# MEchaduino_03.net
KiCad netlist of a schematic drawn in EAGLE
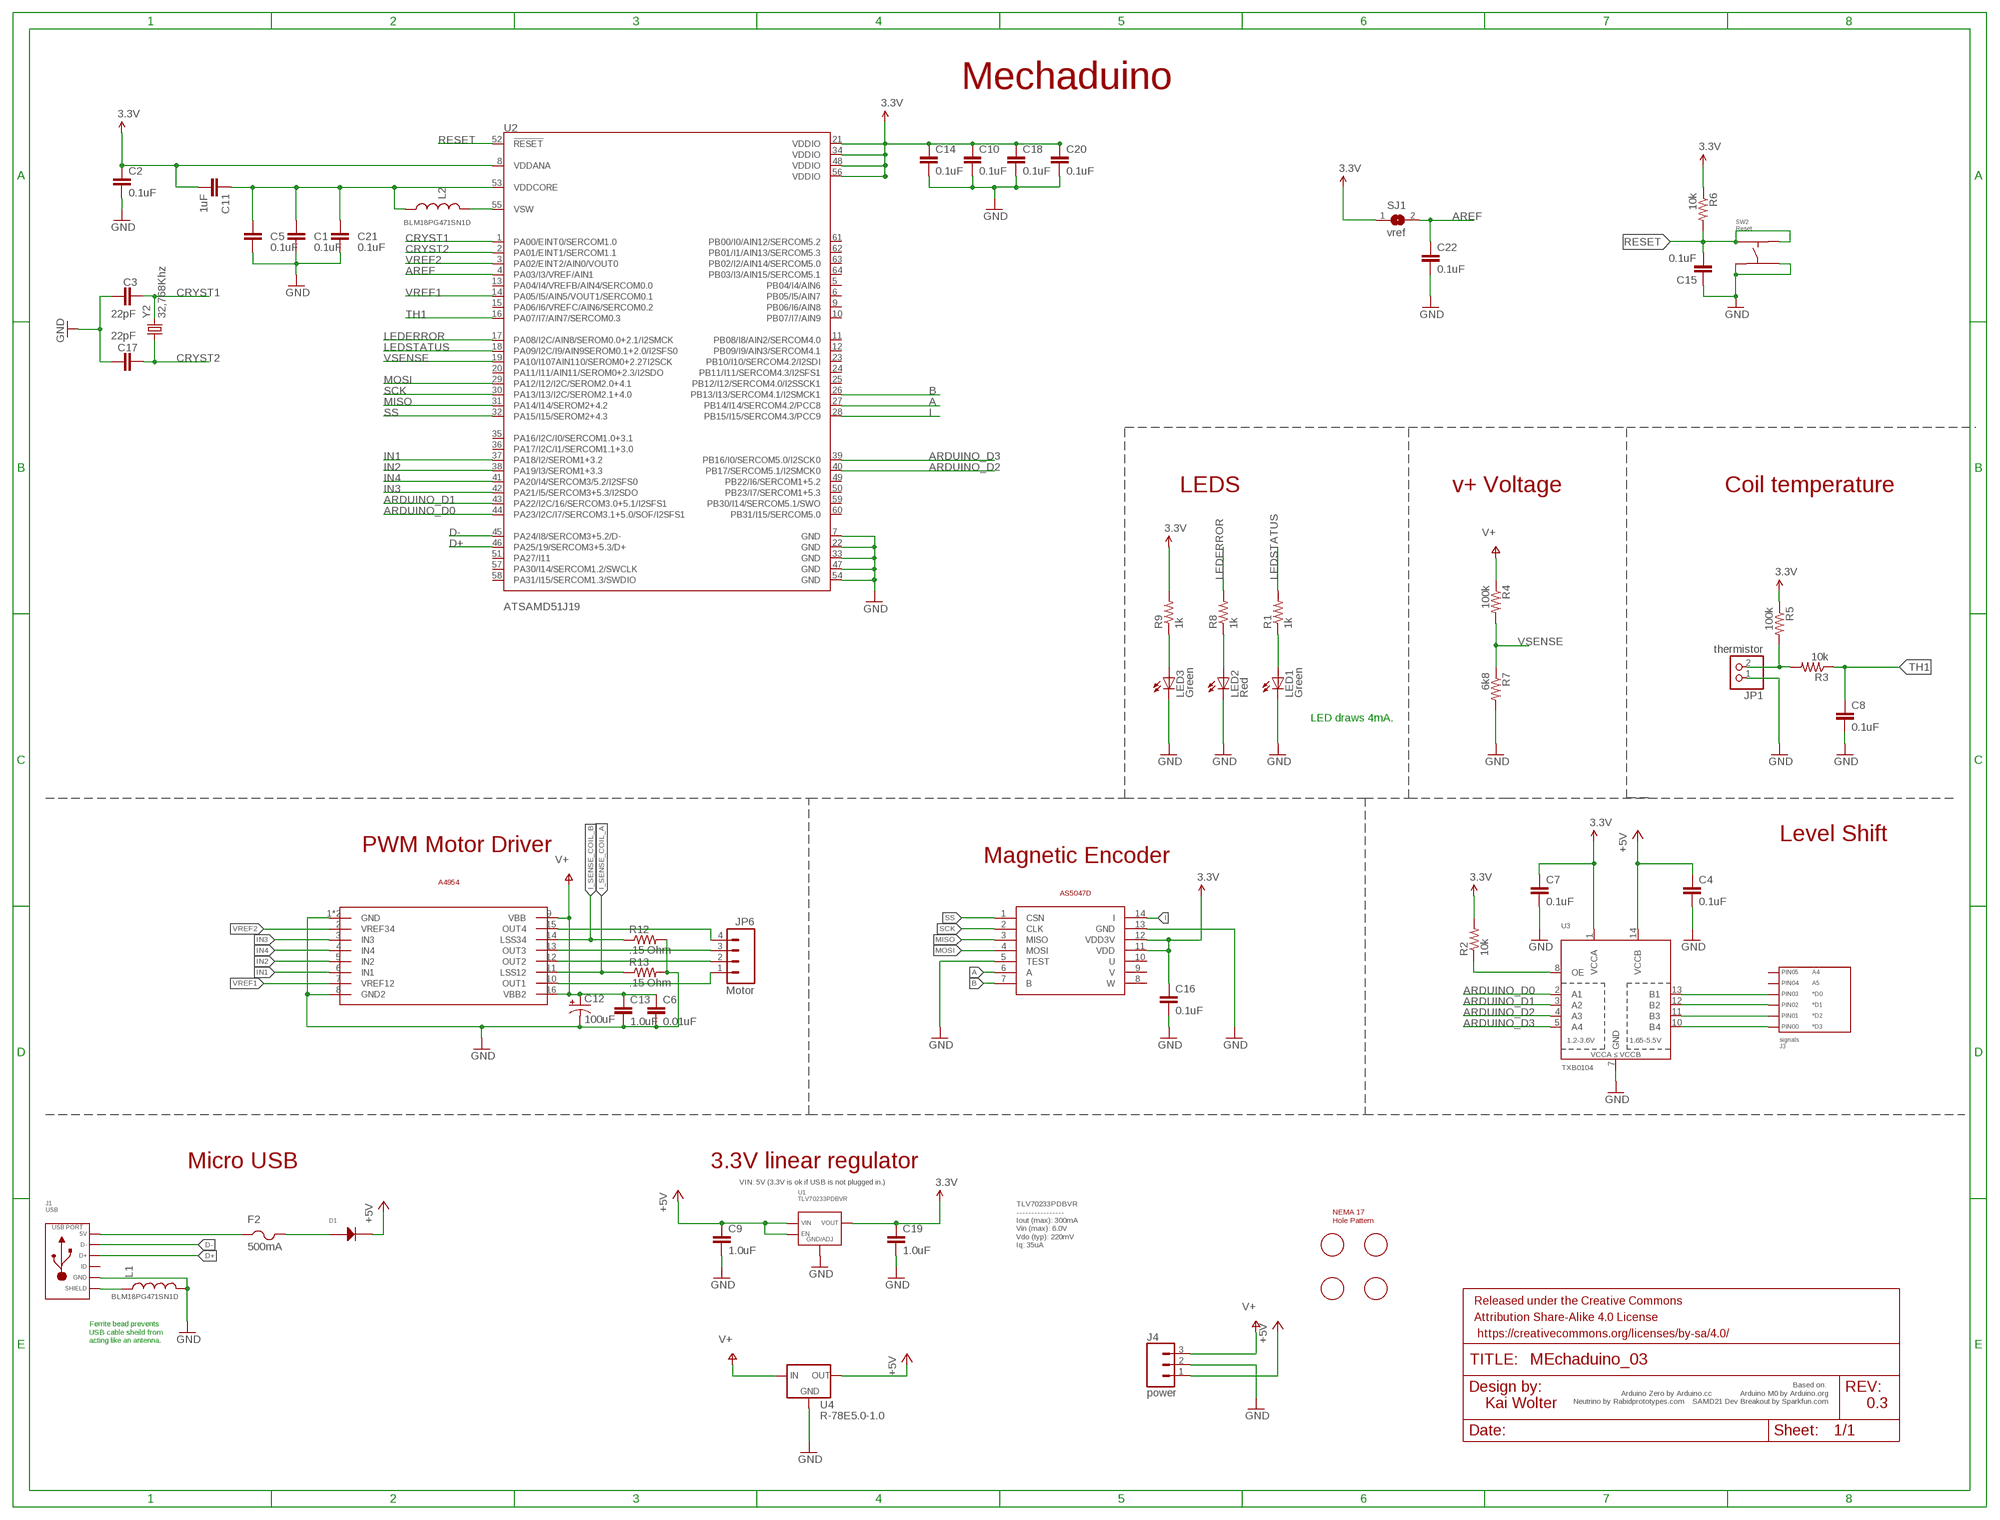
[diagram p0: schematic, sheet 1]

(export (version "E")
  (design (tool "Eeschema 10.0.6"))
  (components
    (comp (ref "C1")
      (value "0.1uF")
      (footprint "eagle-import:0402-CAP")
      (libsource (lib "eagle-import") (part "CAP0402"))
    )
    (comp (ref "C2")
      (value "0.1uF")
      (footprint "eagle-import:0402-CAP")
      (libsource (lib "eagle-import") (part "CAP0402"))
    )
    (comp (ref "C3")
      (value "22pF")
      (footprint "eagle-import:0603-CAP")
      (libsource (lib "eagle-import") (part "CAP0603"))
    )
    (comp (ref "C4")
      (value "0.1uF")
      (footprint "eagle-import:0402-CAP")
      (libsource (lib "eagle-import") (part "CAP0402"))
    )
    (comp (ref "C5")
      (value "0.1uF")
      (footprint "eagle-import:0402-CAP")
      (libsource (lib "eagle-import") (part "CAP0402"))
    )
    (comp (ref "C6")
      (value "0.01uF")
      (footprint "eagle-import:0603-CAP")
      (libsource (lib "eagle-import") (part "CAP0603"))
    )
    (comp (ref "C7")
      (value "0.1uF")
      (footprint "eagle-import:0402-CAP")
      (libsource (lib "eagle-import") (part "CAP0402"))
    )
    (comp (ref "C8")
      (value "0.1uF")
      (footprint "eagle-import:0402-CAP")
      (libsource (lib "eagle-import") (part "CAP0402"))
    )
    (comp (ref "C9")
      (value "1.0uF")
      (footprint "eagle-import:0402-CAP")
      (libsource (lib "eagle-import") (part "CAP0402"))
    )
    (comp (ref "C10")
      (value "0.1uF")
      (footprint "eagle-import:0402-CAP")
      (libsource (lib "eagle-import") (part "CAP0402"))
    )
    (comp (ref "C11")
      (value "1uF")
      (footprint "eagle-import:0402-CAP")
      (libsource (lib "eagle-import") (part "CAP0402"))
    )
    (comp (ref "C12")
      (value "100uF")
      (footprint "eagle-import:PANASONIC_D")
      (libsource (lib "eagle-import") (part "CAP_POLD"))
    )
    (comp (ref "C13")
      (value "1.0uF")
      (footprint "eagle-import:0603-CAP")
      (libsource (lib "eagle-import") (part "CAP0603"))
    )
    (comp (ref "C14")
      (value "0.1uF")
      (footprint "eagle-import:0402-CAP")
      (libsource (lib "eagle-import") (part "CAP0402"))
    )
    (comp (ref "C15")
      (value "0.1uF")
      (footprint "eagle-import:0402-CAP")
      (libsource (lib "eagle-import") (part "CAP0402"))
    )
    (comp (ref "C16")
      (value "0.1uF")
      (footprint "eagle-import:0402-CAP")
      (libsource (lib "eagle-import") (part "CAP0402"))
    )
    (comp (ref "C17")
      (value "22pF")
      (footprint "eagle-import:0603-CAP")
      (libsource (lib "eagle-import") (part "CAP0603"))
    )
    (comp (ref "C18")
      (value "0.1uF")
      (footprint "eagle-import:0402-CAP")
      (libsource (lib "eagle-import") (part "CAP0402"))
    )
    (comp (ref "C19")
      (value "1.0uF")
      (footprint "eagle-import:0402-CAP")
      (libsource (lib "eagle-import") (part "CAP0402"))
    )
    (comp (ref "C20")
      (value "0.1uF")
      (footprint "eagle-import:0402-CAP")
      (libsource (lib "eagle-import") (part "CAP0402"))
    )
    (comp (ref "C21")
      (value "0.1uF")
      (footprint "eagle-import:0402-CAP")
      (libsource (lib "eagle-import") (part "CAP0402"))
    )
    (comp (ref "C22")
      (value "0.1uF")
      (footprint "eagle-import:0402-CAP")
      (libsource (lib "eagle-import") (part "CAP0402"))
    )
    (comp (ref "D1")
      (value "DIODE_SOD-123")
      (footprint "eagle-import:SOD-123")
      (libsource (lib "eagle-import") (part "DIODE_SOD-123"))
    )
    (comp (ref "F2")
      (value "500mA")
      (footprint "eagle-import:R1206")
      (libsource (lib "eagle-import") (part "PTCFUSE-1206"))
    )
    (comp (ref "FRAME1")
      (value "FRAME-LEDGER")
      (footprint "eagle-import:CREATIVE_COMMONS")
      (libsource (lib "eagle-import") (part "FRAME-LEDGER"))
    )
    (comp (ref "J1")
      (value "USB")
      (footprint "eagle-import:MICROUSB-RIGHT")
      (libsource (lib "eagle-import") (part "USB_MICRO_RIGHT"))
    )
    (comp (ref "J3")
      (value "signals")
      (footprint "eagle-import:PTH_2.54MM_01X06")
      (fields
        (field (name "LABEL00") "*D3")
        (field (name "LABEL01") "*D2")
        (field (name "LABEL02") "*D1")
        (field (name "LABEL03") "*D0")
        (field (name "LABEL04") "A5")
        (field (name "LABEL05") "A4")
      )
      (libsource (lib "eagle-import") (part "HEADER_01X06_PTH_2.54MM"))
    )
    (comp (ref "J4")
      (value "power")
      (footprint "eagle-import:1X03")
      (libsource (lib "eagle-import") (part "CONN_03"))
    )
    (comp (ref "JP1")
      (value "thermistor")
      (footprint "eagle-import:1X02")
      (libsource (lib "eagle-import") (part "PINHD-1X2"))
    )
    (comp (ref "JP6")
      (value "Motor")
      (footprint "eagle-import:1X04")
      (libsource (lib "eagle-import") (part "M04PTH"))
    )
    (comp (ref "L1")
      (value "BLM18PG471SN1D")
      (footprint "eagle-import:0603-TDK")
      (libsource (lib "eagle-import") (part "INDUCTOR0603-TDK"))
    )
    (comp (ref "L2")
      (value "BLM18PG471SN1D")
      (footprint "eagle-import:0603-TDK")
      (libsource (lib "eagle-import") (part "INDUCTOR0603-TDK"))
    )
    (comp (ref "LED1")
      (value "Green")
      (footprint "eagle-import:CHIPLED_0805")
      (fields (field (name "PART_NUMBER") "KPT-2012YC"))
      (libsource (lib "eagle-import") (part "0044_KPT-2012YC"))
    )
    (comp (ref "LED2")
      (value "Red")
      (footprint "eagle-import:CHIPLED_0805")
      (fields (field (name "PART_NUMBER") "KPT-2012YC"))
      (libsource (lib "eagle-import") (part "0044_KPT-2012YC"))
    )
    (comp (ref "LED3")
      (value "Green")
      (footprint "eagle-import:CHIPLED_0805")
      (fields (field (name "PART_NUMBER") "KPT-2012YC"))
      (libsource (lib "eagle-import") (part "0044_KPT-2012YC"))
    )
    (comp (ref "R1")
      (value "1k")
      (footprint "eagle-import:R0402")
      (libsource (lib "eagle-import") (part "rcl_334_R-US_R0402"))
    )
    (comp (ref "R2")
      (value "10k")
      (footprint "eagle-import:R0402")
      (libsource (lib "eagle-import") (part "rcl_334_R-US_R0402"))
    )
    (comp (ref "R3")
      (value "10k")
      (footprint "eagle-import:R0402")
      (libsource (lib "eagle-import") (part "rcl_334_R-US_R0402"))
    )
    (comp (ref "R4")
      (value "100k")
      (footprint "eagle-import:R0402")
      (libsource (lib "eagle-import") (part "rcl_334_R-US_R0402"))
    )
    (comp (ref "R5")
      (value "100k")
      (footprint "eagle-import:R0402")
      (libsource (lib "eagle-import") (part "rcl_334_R-US_R0402"))
    )
    (comp (ref "R6")
      (value "10k")
      (footprint "eagle-import:R0402")
      (libsource (lib "eagle-import") (part "rcl_334_R-US_R0402"))
    )
    (comp (ref "R7")
      (value "6k8")
      (footprint "eagle-import:R0402")
      (libsource (lib "eagle-import") (part "rcl_334_R-US_R0402"))
    )
    (comp (ref "R8")
      (value "1k")
      (footprint "eagle-import:R0402")
      (libsource (lib "eagle-import") (part "rcl_334_R-US_R0402"))
    )
    (comp (ref "R9")
      (value "1k")
      (footprint "eagle-import:R0402")
      (libsource (lib "eagle-import") (part "rcl_334_R-US_R0402"))
    )
    (comp (ref "R12")
      (value ".15 Ohm")
      (footprint "eagle-import:R1206")
      (libsource (lib "eagle-import") (part "R-US_R1206"))
    )
    (comp (ref "R13")
      (value ".15 Ohm")
      (footprint "eagle-import:R1206")
      (libsource (lib "eagle-import") (part "R-US_R1206"))
    )
    (comp (ref "SJ1")
      (value "vref")
      (footprint "eagle-import:SJ")
      (libsource (lib "eagle-import") (part "SJ"))
    )
    (comp (ref "SW2")
      (value "Reset")
      (footprint "eagle-import:TACT4.2MM")
      (libsource (lib "eagle-import") (part "TACT_4.2MM"))
    )
    (comp (ref "U$1")
      (value "AVAGO_DRIVERTHERM")
      (footprint "eagle-import:TSSOP16_THERM")
      (libsource (lib "eagle-import") (part "AVAGO_DRIVERTHERM"))
    )
    (comp (ref "U$2")
      (value "NEMA17_HOLE_PATTERNNEW")
      (footprint "eagle-import:NEMA17_HOLE_PATTERN_2")
      (libsource (lib "eagle-import") (part "NEMA17_HOLE_PATTERNNEW"))
    )
    (comp (ref "U$4")
      (value "AS5047D")
      (footprint "eagle-import:TSSOP14")
      (libsource (lib "eagle-import") (part "AS5047D"))
    )
    (comp (ref "U1")
      (value "TLV70233PDBVR")
      (footprint "eagle-import:SOT-23-5")
      (libsource (lib "eagle-import") (part "TLV70233PDBVR"))
    )
    (comp (ref "U2")
      (value "ATSAMD51J19")
      (footprint "eagle-import:TQFP64")
      (libsource (lib "eagle-import") (part "ATSAMD51J19"))
    )
    (comp (ref "U3")
      (value "TXB0104")
      (footprint "eagle-import:TSSOP14")
      (libsource (lib "eagle-import") (part "TXB0104PWR"))
    )
    (comp (ref "U4")
      (value "R-78E5.0-1.0")
      (footprint "eagle-import:DC-DC_CONVERTER_78XX")
      (libsource (lib "eagle-import") (part "R-78E5.0-1.0"))
    )
    (comp (ref "Y2")
      (value "32,768Khz")
      (footprint "eagle-import:CRYSTAL-SMD-2.0X1.2")
      (libsource (lib "eagle-import") (part "CRYSTAL2012"))
    )
  )
  (nets
    (net (code "1") (name "+5V") (class "Default")
      (node (ref "C4") (pin "1") (pinfunction "1_1") (pintype "passive"))
      (node (ref "C9") (pin "1") (pinfunction "1_1") (pintype "passive"))
      (node (ref "D1") (pin "CATHODE") (pinfunction "CATHODE_CATHODE") (pintype "bidirectional"))
      (node (ref "J4") (pin "1") (pinfunction "1_1") (pintype "passive"))
      (node (ref "U1") (pin "P$1") (pinfunction "VIN_P$1") (pintype "bidirectional"))
      (node (ref "U1") (pin "P$3") (pinfunction "EN_P$3") (pintype "bidirectional"))
      (node (ref "U3") (pin "14") (pinfunction "VCCB_14") (pintype "bidirectional"))
      (node (ref "U4") (pin "VOUT") (pinfunction "OUT_VOUT") (pintype "passive"))
    )
    (net (code "2") (name "/ARDUINO_D0") (class "Default")
      (node (ref "U2") (pin "44") (pinfunction "PA23/I2C/I7/SERCOM3.1+5.0/SOF/I2SFS1_44") (pintype "bidirectional"))
      (node (ref "U3") (pin "2") (pinfunction "A1_2") (pintype "bidirectional"))
    )
    (net (code "3") (name "/ARDUINO_D1") (class "Default")
      (node (ref "U2") (pin "43") (pinfunction "PA22/I2C/16/SERCOM3.0+5.1/I2SFS1_43") (pintype "bidirectional"))
      (node (ref "U3") (pin "3") (pinfunction "A2_3") (pintype "bidirectional"))
    )
    (net (code "4") (name "/ARDUINO_D2") (class "Default")
      (node (ref "U2") (pin "40") (pinfunction "PB17/SERCOM5.1/I2SMCK0_40") (pintype "bidirectional"))
      (node (ref "U3") (pin "4") (pinfunction "A3_4") (pintype "bidirectional"))
    )
    (net (code "5") (name "/ARDUINO_D3") (class "Default")
      (node (ref "U2") (pin "39") (pinfunction "PB16/I0/SERCOM5.0/I2SCK0_39") (pintype "bidirectional"))
      (node (ref "U3") (pin "5") (pinfunction "A4_5") (pintype "bidirectional"))
    )
    (net (code "6") (name "/AREF") (class "Default")
      (node (ref "C22") (pin "1") (pinfunction "1_1") (pintype "passive"))
      (node (ref "SJ1") (pin "2") (pinfunction "2_2") (pintype "passive"))
      (node (ref "U2") (pin "4") (pinfunction "PA03/I3/VREF/AIN1_4") (pintype "bidirectional"))
    )
    (net (code "7") (name "/CRYST1") (class "Default")
      (node (ref "C3") (pin "2") (pinfunction "2_2") (pintype "passive"))
      (node (ref "U2") (pin "1") (pinfunction "PA00/EINT0/SERCOM1.0_1") (pintype "bidirectional"))
      (node (ref "Y2") (pin "2") (pinfunction "2_2") (pintype "passive"))
    )
    (net (code "8") (name "/CRYST2") (class "Default")
      (node (ref "C17") (pin "2") (pinfunction "2_2") (pintype "passive"))
      (node (ref "U2") (pin "2") (pinfunction "PA01/EINT1/SERCOM1.1_2") (pintype "bidirectional"))
      (node (ref "Y2") (pin "1") (pinfunction "1_1") (pintype "passive"))
    )
    (net (code "9") (name "/LEDERROR") (class "Default")
      (node (ref "R8") (pin "2") (pinfunction "2_2") (pintype "passive"))
      (node (ref "U2") (pin "17") (pinfunction "PA08/I2C/AIN8/SEROM0.0+2.1/I2SMCK_17") (pintype "bidirectional"))
    )
    (net (code "10") (name "/LEDSTATUS") (class "Default")
      (node (ref "R1") (pin "2") (pinfunction "2_2") (pintype "passive"))
      (node (ref "U2") (pin "18") (pinfunction "PA09/I2C/I9/AIN9SEROM0.1+2.0/I2SFS0_18") (pintype "bidirectional"))
    )
    (net (code "11") (name "/VSENSE") (class "Default")
      (node (ref "R4") (pin "2") (pinfunction "2_2") (pintype "passive"))
      (node (ref "R7") (pin "1") (pinfunction "1_1") (pintype "passive"))
      (node (ref "U2") (pin "19") (pinfunction "PA10/I107AIN110/SEROM0+2.27I2SCK_19") (pintype "bidirectional"))
    )
    (net (code "12") (name "3.3V") (class "Default")
      (node (ref "C10") (pin "1") (pinfunction "1_1") (pintype "passive"))
      (node (ref "C11") (pin "2") (pinfunction "2_2") (pintype "passive"))
      (node (ref "C14") (pin "1") (pinfunction "1_1") (pintype "passive"))
      (node (ref "C16") (pin "1") (pinfunction "1_1") (pintype "passive"))
      (node (ref "C18") (pin "1") (pinfunction "1_1") (pintype "passive"))
      (node (ref "C19") (pin "1") (pinfunction "1_1") (pintype "passive"))
      (node (ref "C2") (pin "1") (pinfunction "1_1") (pintype "passive"))
      (node (ref "C20") (pin "1") (pinfunction "1_1") (pintype "passive"))
      (node (ref "C7") (pin "1") (pinfunction "1_1") (pintype "passive"))
      (node (ref "R2") (pin "2") (pinfunction "2_2") (pintype "passive"))
      (node (ref "R5") (pin "1") (pinfunction "1_1") (pintype "passive"))
      (node (ref "R6") (pin "1") (pinfunction "1_1") (pintype "passive"))
      (node (ref "R9") (pin "2") (pinfunction "2_2") (pintype "passive"))
      (node (ref "SJ1") (pin "1") (pinfunction "1_1") (pintype "passive"))
      (node (ref "U$4") (pin "11") (pinfunction "VDD_11") (pintype "bidirectional"))
      (node (ref "U$4") (pin "12") (pinfunction "VDD3V_12") (pintype "bidirectional"))
      (node (ref "U1") (pin "P$5") (pinfunction "VOUT_P$5") (pintype "bidirectional"))
      (node (ref "U2") (pin "21") (pinfunction "VDDIO_21") (pintype "bidirectional"))
      (node (ref "U2") (pin "34") (pinfunction "VDDIO_34") (pintype "bidirectional"))
      (node (ref "U2") (pin "48") (pinfunction "VDDIO_48") (pintype "bidirectional"))
      (node (ref "U2") (pin "56") (pinfunction "VDDIO_56") (pintype "bidirectional"))
      (node (ref "U2") (pin "8") (pinfunction "VDDANA_8") (pintype "bidirectional"))
      (node (ref "U3") (pin "1") (pinfunction "VCCA_1") (pintype "bidirectional"))
    )
    (net (code "13") (name "A") (class "Default")
      (node (ref "U$4") (pin "6") (pinfunction "A_6") (pintype "bidirectional"))
      (node (ref "U2") (pin "27") (pinfunction "PB14/I14/SERCOM4.2/PCC8_27") (pintype "bidirectional"))
    )
    (net (code "14") (name "B") (class "Default")
      (node (ref "U$4") (pin "7") (pinfunction "B_7") (pintype "bidirectional"))
      (node (ref "U2") (pin "26") (pinfunction "PB13/I13/SERCOM4.1/I2SMCK1_26") (pintype "bidirectional"))
    )
    (net (code "15") (name "D+") (class "Default")
      (node (ref "J1") (pin "3") (pinfunction "D+_3") (pintype "bidirectional"))
      (node (ref "U2") (pin "46") (pinfunction "PA25/19/SERCOM3+5.3/D+_46") (pintype "bidirectional"))
    )
    (net (code "16") (name "D-") (class "Default")
      (node (ref "J1") (pin "2") (pinfunction "D-_2") (pintype "bidirectional"))
      (node (ref "U2") (pin "45") (pinfunction "PA24/I8/SERCOM3+5.2/D-_45") (pintype "bidirectional"))
    )
    (net (code "17") (name "GND") (class "Default")
      (node (ref "C1") (pin "2") (pinfunction "2_2") (pintype "passive"))
      (node (ref "C10") (pin "2") (pinfunction "2_2") (pintype "passive"))
      (node (ref "C12") (pin "-") (pinfunction "-_-") (pintype "passive"))
      (node (ref "C13") (pin "2") (pinfunction "2_2") (pintype "passive"))
      (node (ref "C14") (pin "2") (pinfunction "2_2") (pintype "passive"))
      (node (ref "C15") (pin "1") (pinfunction "1_1") (pintype "passive"))
      (node (ref "C16") (pin "2") (pinfunction "2_2") (pintype "passive"))
      (node (ref "C17") (pin "1") (pinfunction "1_1") (pintype "passive"))
      (node (ref "C18") (pin "2") (pinfunction "2_2") (pintype "passive"))
      (node (ref "C19") (pin "2") (pinfunction "2_2") (pintype "passive"))
      (node (ref "C2") (pin "2") (pinfunction "2_2") (pintype "passive"))
      (node (ref "C20") (pin "2") (pinfunction "2_2") (pintype "passive"))
      (node (ref "C21") (pin "2") (pinfunction "2_2") (pintype "passive"))
      (node (ref "C22") (pin "2") (pinfunction "2_2") (pintype "passive"))
      (node (ref "C3") (pin "1") (pinfunction "1_1") (pintype "passive"))
      (node (ref "C4") (pin "2") (pinfunction "2_2") (pintype "passive"))
      (node (ref "C5") (pin "2") (pinfunction "2_2") (pintype "passive"))
      (node (ref "C6") (pin "2") (pinfunction "2_2") (pintype "passive"))
      (node (ref "C7") (pin "2") (pinfunction "2_2") (pintype "passive"))
      (node (ref "C8") (pin "2") (pinfunction "2_2") (pintype "passive"))
      (node (ref "C9") (pin "2") (pinfunction "2_2") (pintype "passive"))
      (node (ref "J1") (pin "5") (pinfunction "GND_5") (pintype "power_in"))
      (node (ref "J4") (pin "2") (pinfunction "2_2") (pintype "passive"))
      (node (ref "JP1") (pin "1") (pinfunction "1_1") (pintype "passive"))
      (node (ref "L1") (pin "2") (pinfunction "2_2") (pintype "passive"))
      (node (ref "LED1") (pin "C") (pinfunction "C_C") (pintype "passive"))
      (node (ref "LED2") (pin "C") (pinfunction "C_C") (pintype "passive"))
      (node (ref "LED3") (pin "C") (pinfunction "C_C") (pintype "passive"))
      (node (ref "R12") (pin "2") (pinfunction "2_2") (pintype "passive"))
      (node (ref "R13") (pin "2") (pinfunction "2_2") (pintype "passive"))
      (node (ref "R7") (pin "2") (pinfunction "2_2") (pintype "passive"))
      (node (ref "SW2") (pin "P$3") (pinfunction "P$3_P$3") (pintype "bidirectional"))
      (node (ref "SW2") (pin "P$4") (pinfunction "P$4_P$4") (pintype "bidirectional"))
      (node (ref "U$1") (pin "1") (pinfunction "GND_1") (pintype "bidirectional"))
      (node (ref "U$1") (pin "8") (pinfunction "GND2_8") (pintype "bidirectional"))
      (node (ref "U$1") (pin "P$1") (pinfunction "GND_P$1") (pintype "bidirectional"))
      (node (ref "U$4") (pin "13") (pinfunction "GND_13") (pintype "bidirectional"))
      (node (ref "U$4") (pin "5") (pinfunction "TEST_5") (pintype "bidirectional"))
      (node (ref "U1") (pin "P$2") (pinfunction "GND/ADJ_P$2") (pintype "bidirectional"))
      (node (ref "U2") (pin "22") (pinfunction "GND_22") (pintype "bidirectional"))
      (node (ref "U2") (pin "33") (pinfunction "GND_33") (pintype "bidirectional"))
      (node (ref "U2") (pin "47") (pinfunction "GND_47") (pintype "bidirectional"))
      (node (ref "U2") (pin "54") (pinfunction "GND_54") (pintype "bidirectional"))
      (node (ref "U2") (pin "7") (pinfunction "GND_7") (pintype "bidirectional"))
      (node (ref "U3") (pin "7") (pinfunction "GND_7") (pintype "bidirectional"))
      (node (ref "U4") (pin "GND") (pinfunction "GND_GND") (pintype "input"))
    )
    (net (code "18") (name "I") (class "Default")
      (node (ref "U$4") (pin "14") (pinfunction "I_14") (pintype "bidirectional"))
      (node (ref "U2") (pin "28") (pinfunction "PB15/I15/SERCOM4.3/PCC9_28") (pintype "bidirectional"))
    )
    (net (code "19") (name "IN1") (class "Default")
      (node (ref "U$1") (pin "6") (pinfunction "IN1_6") (pintype "bidirectional"))
      (node (ref "U2") (pin "37") (pinfunction "PA18/I2/SEROM1+3.2_37") (pintype "bidirectional"))
    )
    (net (code "20") (name "IN2") (class "Default")
      (node (ref "U$1") (pin "5") (pinfunction "IN2_5") (pintype "bidirectional"))
      (node (ref "U2") (pin "38") (pinfunction "PA19/I3/SEROM1+3.3_38") (pintype "bidirectional"))
    )
    (net (code "21") (name "IN3") (class "Default")
      (node (ref "U$1") (pin "3") (pinfunction "IN3_3") (pintype "bidirectional"))
      (node (ref "U2") (pin "42") (pinfunction "PA21/I5/SERCOM3+5.3/I2SDO_42") (pintype "bidirectional"))
    )
    (net (code "22") (name "IN4") (class "Default")
      (node (ref "U$1") (pin "4") (pinfunction "IN4_4") (pintype "bidirectional"))
      (node (ref "U2") (pin "41") (pinfunction "PA20/I4/SERCOM3/5.2/I2SFS0_41") (pintype "bidirectional"))
    )
    (net (code "23") (name "I_SENSE_COIL_A") (class "Default")
      (node (ref "R13") (pin "1") (pinfunction "1_1") (pintype "passive"))
      (node (ref "U$1") (pin "11") (pinfunction "LSS12_11") (pintype "bidirectional"))
    )
    (net (code "24") (name "I_SENSE_COIL_B") (class "Default")
      (node (ref "R12") (pin "1") (pinfunction "1_1") (pintype "passive"))
      (node (ref "U$1") (pin "14") (pinfunction "LSS34_14") (pintype "bidirectional"))
    )
    (net (code "25") (name "MISO") (class "Default")
      (node (ref "U$4") (pin "3") (pinfunction "MISO_3") (pintype "bidirectional"))
      (node (ref "U2") (pin "31") (pinfunction "PA14/I14/SEROM2+4.2_31") (pintype "bidirectional"))
    )
    (net (code "26") (name "MOSI") (class "Default")
      (node (ref "U$4") (pin "4") (pinfunction "MOSI_4") (pintype "bidirectional"))
      (node (ref "U2") (pin "29") (pinfunction "PA12/I12/I2C/SEROM2.0+4.1_29") (pintype "bidirectional"))
    )
    (net (code "27") (name "Net-(D1-PadANODE)") (class "Default")
      (node (ref "D1") (pin "ANODE") (pinfunction "ANODE_ANODE") (pintype "bidirectional"))
      (node (ref "F2") (pin "2") (pinfunction "2_2") (pintype "passive"))
    )
    (net (code "28") (name "Net-(J1-5V)") (class "Default")
      (node (ref "F2") (pin "1") (pinfunction "1_1") (pintype "passive"))
      (node (ref "J1") (pin "1") (pinfunction "5V_1") (pintype "power_in"))
    )
    (net (code "29") (name "Net-(J1-SLD-PadS1)") (class "Default")
      (node (ref "J1") (pin "S1") (pinfunction "SLD_S1") (pintype "power_in"))
      (node (ref "J1") (pin "S2") (pinfunction "SLD_S2") (pintype "power_in"))
      (node (ref "J1") (pin "S3") (pinfunction "SLD_S3") (pintype "power_in"))
      (node (ref "J1") (pin "S4") (pinfunction "SLD_S4") (pintype "power_in"))
      (node (ref "J1") (pin "S5") (pinfunction "SLD_S5") (pintype "power_in"))
      (node (ref "J1") (pin "S6") (pinfunction "SLD_S6") (pintype "power_in"))
      (node (ref "J1") (pin "S7") (pinfunction "SLD_S7") (pintype "power_in"))
      (node (ref "J1") (pin "S8") (pinfunction "SLD_S8") (pintype "power_in"))
      (node (ref "L1") (pin "1") (pinfunction "1_1") (pintype "passive"))
    )
    (net (code "30") (name "Net-(J3-PIN0)") (class "Default")
      (node (ref "J3") (pin "P$1") (pinfunction "PIN0_P$1") (pintype "bidirectional"))
      (node (ref "U3") (pin "10") (pinfunction "B4_10") (pintype "bidirectional"))
    )
    (net (code "31") (name "Net-(J3-PIN1)") (class "Default")
      (node (ref "J3") (pin "P$2") (pinfunction "PIN1_P$2") (pintype "bidirectional"))
      (node (ref "U3") (pin "11") (pinfunction "B3_11") (pintype "bidirectional"))
    )
    (net (code "32") (name "Net-(J3-PIN2)") (class "Default")
      (node (ref "J3") (pin "P$3") (pinfunction "PIN2_P$3") (pintype "bidirectional"))
      (node (ref "U3") (pin "12") (pinfunction "B2_12") (pintype "bidirectional"))
    )
    (net (code "33") (name "Net-(J3-PIN3)") (class "Default")
      (node (ref "J3") (pin "P$4") (pinfunction "PIN3_P$4") (pintype "bidirectional"))
      (node (ref "U3") (pin "13") (pinfunction "B1_13") (pintype "bidirectional"))
    )
    (net (code "34") (name "Net-(JP1-Pad2)") (class "Default")
      (node (ref "JP1") (pin "2") (pinfunction "2_2") (pintype "passive"))
      (node (ref "R3") (pin "2") (pinfunction "2_2") (pintype "passive"))
      (node (ref "R5") (pin "2") (pinfunction "2_2") (pintype "passive"))
    )
    (net (code "35") (name "Net-(LED1-PadA)") (class "Default")
      (node (ref "LED1") (pin "A") (pinfunction "A_A") (pintype "passive"))
      (node (ref "R1") (pin "1") (pinfunction "1_1") (pintype "passive"))
    )
    (net (code "36") (name "Net-(LED2-PadA)") (class "Default")
      (node (ref "LED2") (pin "A") (pinfunction "A_A") (pintype "passive"))
      (node (ref "R8") (pin "1") (pinfunction "1_1") (pintype "passive"))
    )
    (net (code "37") (name "Net-(LED3-PadA)") (class "Default")
      (node (ref "LED3") (pin "A") (pinfunction "A_A") (pintype "passive"))
      (node (ref "R9") (pin "1") (pinfunction "1_1") (pintype "passive"))
    )
    (net (code "38") (name "Net-(U$1-OUT1)") (class "Default")
      (node (ref "JP6") (pin "1") (pinfunction "1_1") (pintype "passive"))
      (node (ref "U$1") (pin "10") (pinfunction "OUT1_10") (pintype "bidirectional"))
    )
    (net (code "39") (name "Net-(U$1-OUT2)") (class "Default")
      (node (ref "JP6") (pin "2") (pinfunction "2_2") (pintype "passive"))
      (node (ref "U$1") (pin "12") (pinfunction "OUT2_12") (pintype "bidirectional"))
    )
    (net (code "40") (name "Net-(U$1-OUT3)") (class "Default")
      (node (ref "JP6") (pin "3") (pinfunction "3_3") (pintype "passive"))
      (node (ref "U$1") (pin "13") (pinfunction "OUT3_13") (pintype "bidirectional"))
    )
    (net (code "41") (name "Net-(U$1-OUT4)") (class "Default")
      (node (ref "JP6") (pin "4") (pinfunction "4_4") (pintype "passive"))
      (node (ref "U$1") (pin "15") (pinfunction "OUT4_15") (pintype "bidirectional"))
    )
    (net (code "42") (name "Net-(U2-VDDCORE)") (class "Default")
      (node (ref "C1") (pin "1") (pinfunction "1_1") (pintype "passive"))
      (node (ref "C11") (pin "1") (pinfunction "1_1") (pintype "passive"))
      (node (ref "C21") (pin "1") (pinfunction "1_1") (pintype "passive"))
      (node (ref "C5") (pin "1") (pinfunction "1_1") (pintype "passive"))
      (node (ref "L2") (pin "1") (pinfunction "1_1") (pintype "passive"))
      (node (ref "U2") (pin "53") (pinfunction "VDDCORE_53") (pintype "bidirectional"))
    )
    (net (code "43") (name "Net-(U2-VSW)") (class "Default")
      (node (ref "L2") (pin "2") (pinfunction "2_2") (pintype "passive"))
      (node (ref "U2") (pin "55") (pinfunction "VSW_55") (pintype "bidirectional"))
    )
    (net (code "44") (name "Net-(U3-OE)") (class "Default")
      (node (ref "R2") (pin "1") (pinfunction "1_1") (pintype "passive"))
      (node (ref "U3") (pin "8") (pinfunction "OE_8") (pintype "bidirectional"))
    )
    (net (code "45") (name "RESET") (class "Default")
      (node (ref "C15") (pin "2") (pinfunction "2_2") (pintype "passive"))
      (node (ref "R6") (pin "2") (pinfunction "2_2") (pintype "passive"))
      (node (ref "SW2") (pin "P$1") (pinfunction "P$1_P$1") (pintype "bidirectional"))
      (node (ref "SW2") (pin "P$2") (pinfunction "P$2_P$2") (pintype "bidirectional"))
      (node (ref "U2") (pin "52") (pinfunction "~{RESET}_52") (pintype "bidirectional"))
    )
    (net (code "46") (name "SCK") (class "Default")
      (node (ref "U$4") (pin "2") (pinfunction "CLK_2") (pintype "bidirectional"))
      (node (ref "U2") (pin "30") (pinfunction "PA13/I13/I2C/SEROM2.1+4.0_30") (pintype "bidirectional"))
    )
    (net (code "47") (name "SS") (class "Default")
      (node (ref "U$4") (pin "1") (pinfunction "CSN_1") (pintype "bidirectional"))
      (node (ref "U2") (pin "32") (pinfunction "PA15/I15/SEROM2+4.3_32") (pintype "bidirectional"))
    )
    (net (code "48") (name "TH1") (class "Default")
      (node (ref "C8") (pin "1") (pinfunction "1_1") (pintype "passive"))
      (node (ref "R3") (pin "1") (pinfunction "1_1") (pintype "passive"))
      (node (ref "U2") (pin "16") (pinfunction "PA07/I7/AIN7/SERCOM0.3_16") (pintype "bidirectional"))
    )
    (net (code "49") (name "V+") (class "Default")
      (node (ref "C12") (pin "+") (pinfunction "+_+") (pintype "passive"))
      (node (ref "C13") (pin "1") (pinfunction "1_1") (pintype "passive"))
      (node (ref "C6") (pin "1") (pinfunction "1_1") (pintype "passive"))
      (node (ref "J4") (pin "3") (pinfunction "3_3") (pintype "passive"))
      (node (ref "R4") (pin "1") (pinfunction "1_1") (pintype "passive"))
      (node (ref "U$1") (pin "16") (pinfunction "VBB2_16") (pintype "bidirectional"))
      (node (ref "U$1") (pin "9") (pinfunction "VBB_9") (pintype "bidirectional"))
      (node (ref "U4") (pin "VIN") (pinfunction "IN_VIN") (pintype "input"))
    )
    (net (code "50") (name "VREF1") (class "Default")
      (node (ref "U$1") (pin "7") (pinfunction "VREF12_7") (pintype "bidirectional"))
      (node (ref "U2") (pin "14") (pinfunction "PA05/I5/AIN5/VOUT1/SERCOM0.1_14") (pintype "bidirectional"))
    )
    (net (code "51") (name "VREF2") (class "Default")
      (node (ref "U$1") (pin "2") (pinfunction "VREF34_2") (pintype "bidirectional"))
      (node (ref "U2") (pin "3") (pinfunction "PA02/EINT2/AIN0/VOUT0_3") (pintype "bidirectional"))
    )
    (net (code "52") (name "unconnected-(J1-ID-Pad4)") (class "Default")
      (node (ref "J1") (pin "4") (pinfunction "ID_4") (pintype "bidirectional"))
    )
    (net (code "53") (name "unconnected-(J3-PIN4-PadP$5)") (class "Default")
      (node (ref "J3") (pin "P$5") (pinfunction "PIN4_P$5") (pintype "bidirectional"))
    )
    (net (code "54") (name "unconnected-(J3-PIN5-PadP$6)") (class "Default")
      (node (ref "J3") (pin "P$6") (pinfunction "PIN5_P$6") (pintype "bidirectional"))
    )
    (net (code "55") (name "unconnected-(U$4-U-Pad10)") (class "Default")
      (node (ref "U$4") (pin "10") (pinfunction "U_10") (pintype "bidirectional"))
    )
    (net (code "56") (name "unconnected-(U$4-V-Pad9)") (class "Default")
      (node (ref "U$4") (pin "9") (pinfunction "V_9") (pintype "bidirectional"))
    )
    (net (code "57") (name "unconnected-(U$4-W-Pad8)") (class "Default")
      (node (ref "U$4") (pin "8") (pinfunction "W_8") (pintype "bidirectional"))
    )
    (net (code "58") (name "unconnected-(U2-PA04{slash}I4{slash}VREFB{slash}AIN4{slash}SERCOM0.0-Pad13)") (class "Default")
      (node (ref "U2") (pin "13") (pinfunction "PA04/I4/VREFB/AIN4/SERCOM0.0_13") (pintype "bidirectional"))
    )
    (net (code "59") (name "unconnected-(U2-PA06{slash}I6{slash}VREFC{slash}AIN6{slash}SERCOM0.2-Pad15)") (class "Default")
      (node (ref "U2") (pin "15") (pinfunction "PA06/I6/VREFC/AIN6/SERCOM0.2_15") (pintype "bidirectional"))
    )
    (net (code "60") (name "unconnected-(U2-PA11{slash}I11{slash}AIN11{slash}SEROM0+2.3{slash}I2SDO-Pad20)") (class "Default")
      (node (ref "U2") (pin "20") (pinfunction "PA11/I11/AIN11/SEROM0+2.3/I2SDO_20") (pintype "bidirectional"))
    )
    (net (code "61") (name "unconnected-(U2-PA16{slash}I2C{slash}I0{slash}SERCOM1.0+3.1-Pad35)") (class "Default")
      (node (ref "U2") (pin "35") (pinfunction "PA16/I2C/I0/SERCOM1.0+3.1_35") (pintype "bidirectional"))
    )
    (net (code "62") (name "unconnected-(U2-PA17{slash}I2C{slash}I1{slash}SERCOM1.1+3.0-Pad36)") (class "Default")
      (node (ref "U2") (pin "36") (pinfunction "PA17/I2C/I1/SERCOM1.1+3.0_36") (pintype "bidirectional"))
    )
    (net (code "63") (name "unconnected-(U2-PA27{slash}I11-Pad51)") (class "Default")
      (node (ref "U2") (pin "51") (pinfunction "PA27/I11_51") (pintype "bidirectional"))
    )
    (net (code "64") (name "unconnected-(U2-PA30{slash}I14{slash}SERCOM1.2{slash}SWCLK-Pad57)") (class "Default")
      (node (ref "U2") (pin "57") (pinfunction "PA30/I14/SERCOM1.2/SWCLK_57") (pintype "bidirectional"))
    )
    (net (code "65") (name "unconnected-(U2-PA31{slash}I15{slash}SERCOM1.3{slash}SWDIO-Pad58)") (class "Default")
      (node (ref "U2") (pin "58") (pinfunction "PA31/I15/SERCOM1.3/SWDIO_58") (pintype "bidirectional"))
    )
    (net (code "66") (name "unconnected-(U2-PB00{slash}I0{slash}AIN12{slash}SERCOM5.2-Pad61)") (class "Default")
      (node (ref "U2") (pin "61") (pinfunction "PB00/I0/AIN12/SERCOM5.2_61") (pintype "bidirectional"))
    )
    (net (code "67") (name "unconnected-(U2-PB01{slash}I1{slash}AIN13{slash}SERCOM5.3-Pad62)") (class "Default")
      (node (ref "U2") (pin "62") (pinfunction "PB01/I1/AIN13/SERCOM5.3_62") (pintype "bidirectional"))
    )
    (net (code "68") (name "unconnected-(U2-PB02{slash}I2{slash}AIN14{slash}SERCOM5.0-Pad63)") (class "Default")
      (node (ref "U2") (pin "63") (pinfunction "PB02/I2/AIN14/SERCOM5.0_63") (pintype "bidirectional"))
    )
    (net (code "69") (name "unconnected-(U2-PB03{slash}I3{slash}AIN15{slash}SERCOM5.1-Pad64)") (class "Default")
      (node (ref "U2") (pin "64") (pinfunction "PB03/I3/AIN15/SERCOM5.1_64") (pintype "bidirectional"))
    )
    (net (code "70") (name "unconnected-(U2-PB04{slash}I4{slash}AIN6-Pad5)") (class "Default")
      (node (ref "U2") (pin "5") (pinfunction "PB04/I4/AIN6_5") (pintype "bidirectional"))
    )
    (net (code "71") (name "unconnected-(U2-PB05{slash}I5{slash}AIN7-Pad6)") (class "Default")
      (node (ref "U2") (pin "6") (pinfunction "PB05/I5/AIN7_6") (pintype "bidirectional"))
    )
    (net (code "72") (name "unconnected-(U2-PB06{slash}I6{slash}AIN8-Pad9)") (class "Default")
      (node (ref "U2") (pin "9") (pinfunction "PB06/I6/AIN8_9") (pintype "bidirectional"))
    )
    (net (code "73") (name "unconnected-(U2-PB07{slash}I7{slash}AIN9-Pad10)") (class "Default")
      (node (ref "U2") (pin "10") (pinfunction "PB07/I7/AIN9_10") (pintype "bidirectional"))
    )
    (net (code "74") (name "unconnected-(U2-PB08{slash}I8{slash}AIN2{slash}SERCOM4.0-Pad11)") (class "Default")
      (node (ref "U2") (pin "11") (pinfunction "PB08/I8/AIN2/SERCOM4.0_11") (pintype "bidirectional"))
    )
    (net (code "75") (name "unconnected-(U2-PB09{slash}I9{slash}AIN3{slash}SERCOM4.1-Pad12)") (class "Default")
      (node (ref "U2") (pin "12") (pinfunction "PB09/I9/AIN3/SERCOM4.1_12") (pintype "bidirectional"))
    )
    (net (code "76") (name "unconnected-(U2-PB10{slash}I10{slash}SERCOM4.2{slash}I2SDI-Pad23)") (class "Default")
      (node (ref "U2") (pin "23") (pinfunction "PB10/I10/SERCOM4.2/I2SDI_23") (pintype "bidirectional"))
    )
    (net (code "77") (name "unconnected-(U2-PB11{slash}I11{slash}SERCOM4.3{slash}I2SFS1-Pad24)") (class "Default")
      (node (ref "U2") (pin "24") (pinfunction "PB11/I11/SERCOM4.3/I2SFS1_24") (pintype "bidirectional"))
    )
    (net (code "78") (name "unconnected-(U2-PB12{slash}I12{slash}SERCOM4.0{slash}I2SSCK1-Pad25)") (class "Default")
      (node (ref "U2") (pin "25") (pinfunction "PB12/I12/SERCOM4.0/I2SSCK1_25") (pintype "bidirectional"))
    )
    (net (code "79") (name "unconnected-(U2-PB22{slash}I6{slash}SERCOM1+5.2-Pad49)") (class "Default")
      (node (ref "U2") (pin "49") (pinfunction "PB22/I6/SERCOM1+5.2_49") (pintype "bidirectional"))
    )
    (net (code "80") (name "unconnected-(U2-PB23{slash}I7{slash}SERCOM1+5.3-Pad50)") (class "Default")
      (node (ref "U2") (pin "50") (pinfunction "PB23/I7/SERCOM1+5.3_50") (pintype "bidirectional"))
    )
    (net (code "81") (name "unconnected-(U2-PB30{slash}I14{slash}SERCOM5.1{slash}SWO-Pad59)") (class "Default")
      (node (ref "U2") (pin "59") (pinfunction "PB30/I14/SERCOM5.1/SWO_59") (pintype "bidirectional"))
    )
    (net (code "82") (name "unconnected-(U2-PB31{slash}I15{slash}SERCOM5.0-Pad60)") (class "Default")
      (node (ref "U2") (pin "60") (pinfunction "PB31/I15/SERCOM5.0_60") (pintype "bidirectional"))
    )
  )
)
